# tx.net
KiCad netlist of a schematic drawn in EAGLE
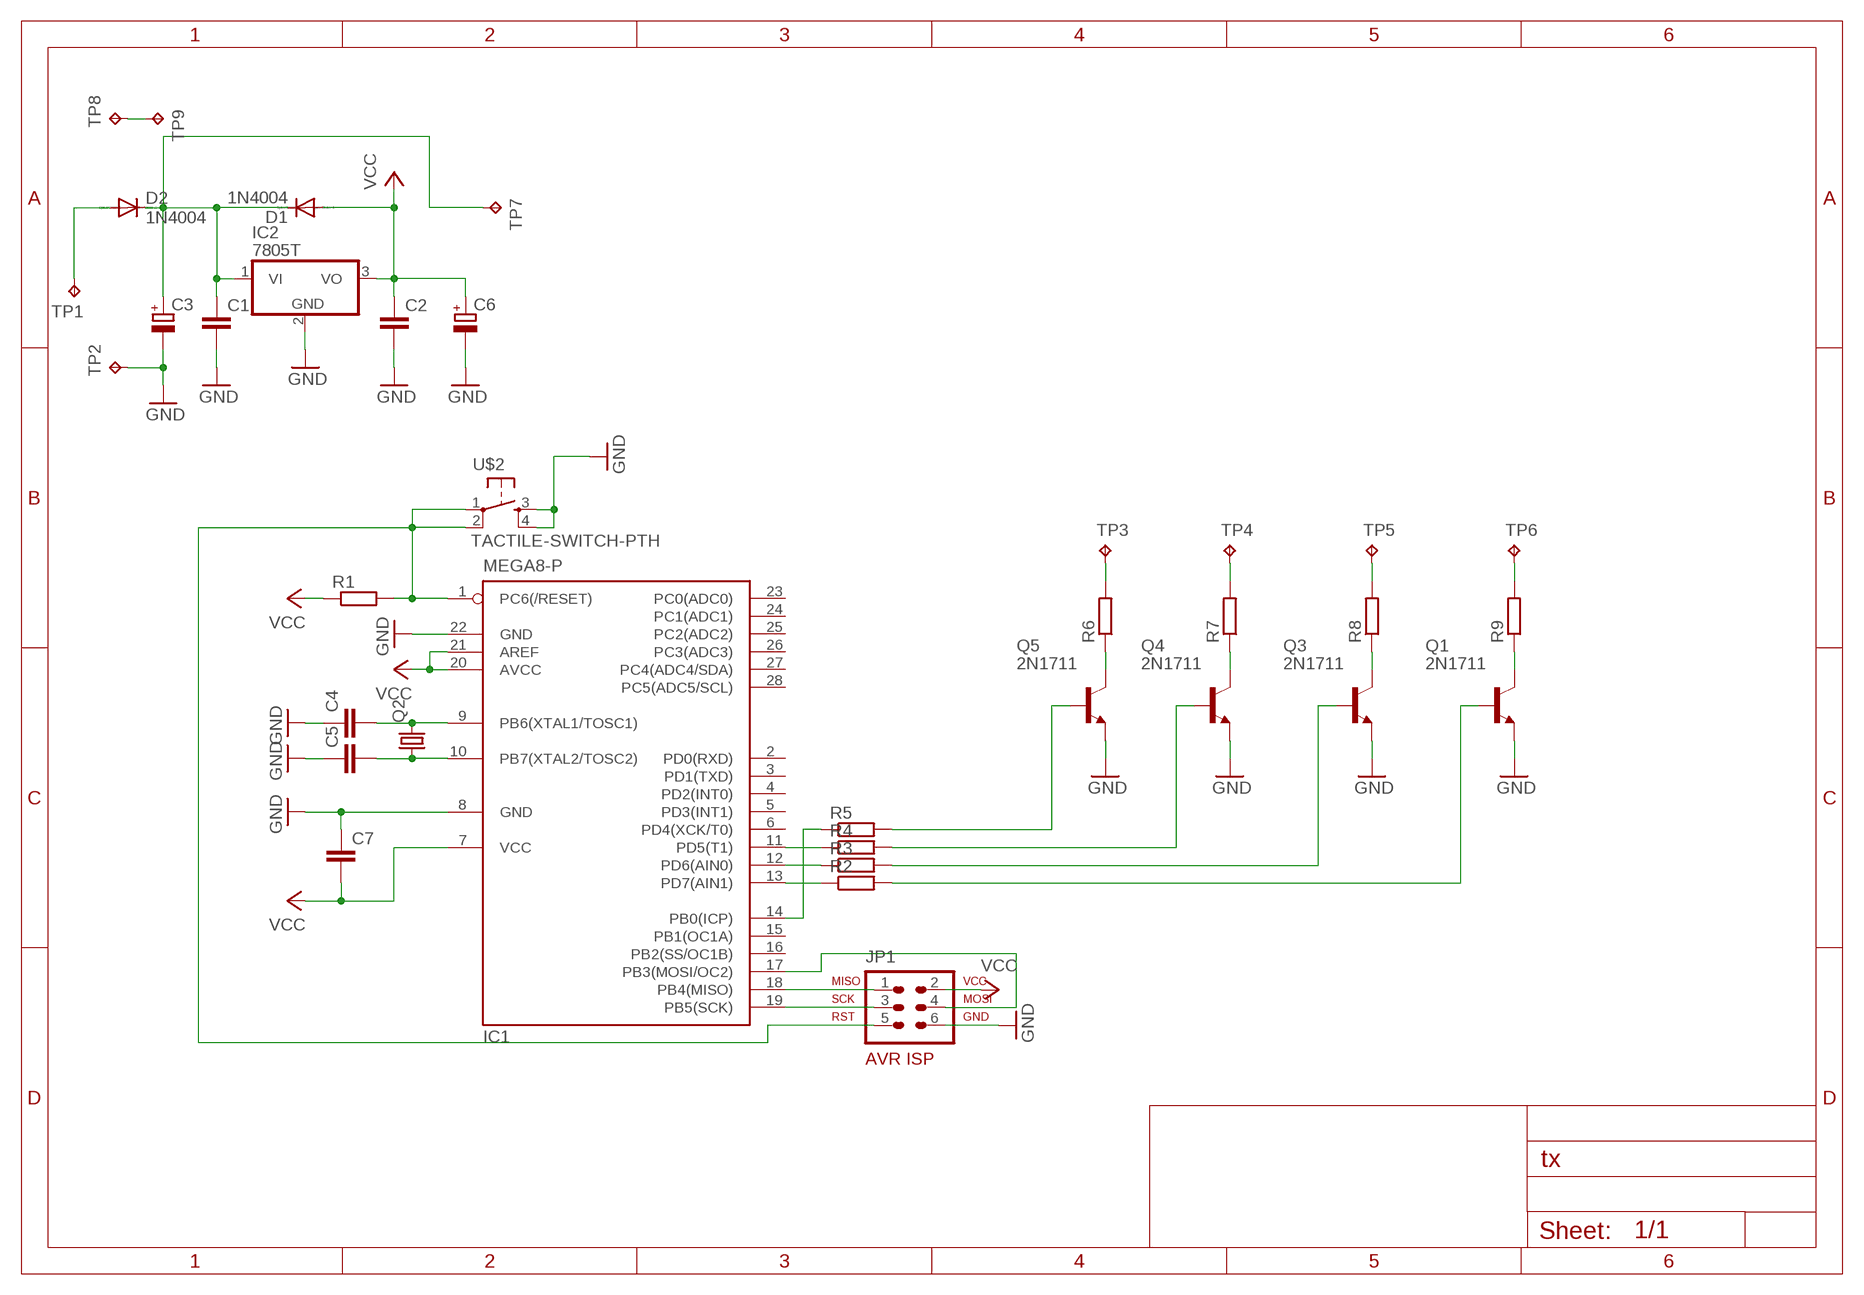
[diagram p0: schematic, sheet 1]

(export (version "E")
  (design (tool "Eeschema 10.0.6"))
  (components
    (comp (ref "C1")
      (value "C-EU050-030X075")
      (footprint "eagle-import:C050-030X075")
      (libsource (lib "eagle-import") (part "C-EU050-030X075"))
    )
    (comp (ref "C2")
      (value "C-EU050-030X075")
      (footprint "eagle-import:C050-030X075")
      (libsource (lib "eagle-import") (part "C-EU050-030X075"))
    )
    (comp (ref "C3")
      (value "CPOL-EUE3.5-8")
      (footprint "eagle-import:E3,5-8")
      (libsource (lib "eagle-import") (part "CPOL-EUE3.5-8"))
    )
    (comp (ref "C4")
      (value "C-EU050-030X075")
      (footprint "eagle-import:C050-030X075")
      (libsource (lib "eagle-import") (part "C-EU050-030X075"))
    )
    (comp (ref "C5")
      (value "C-EU050-030X075")
      (footprint "eagle-import:C050-030X075")
      (libsource (lib "eagle-import") (part "C-EU050-030X075"))
    )
    (comp (ref "C6")
      (value "CPOL-EUE3.5-8")
      (footprint "eagle-import:E3,5-8")
      (libsource (lib "eagle-import") (part "CPOL-EUE3.5-8"))
    )
    (comp (ref "C7")
      (value "C-EU050-030X075")
      (footprint "eagle-import:C050-030X075")
      (libsource (lib "eagle-import") (part "C-EU050-030X075"))
    )
    (comp (ref "D1")
      (value "1N4004")
      (footprint "eagle-import:DO41-10")
      (libsource (lib "eagle-import") (part "1N4004"))
    )
    (comp (ref "D2")
      (value "1N4004")
      (footprint "eagle-import:DO41-10")
      (libsource (lib "eagle-import") (part "1N4004"))
    )
    (comp (ref "IC1")
      (value "MEGA8-P")
      (footprint "eagle-import:DIL28-3")
      (libsource (lib "eagle-import") (part "MEGA8-P"))
    )
    (comp (ref "IC2")
      (value "7805T")
      (footprint "eagle-import:TO220H")
      (libsource (lib "eagle-import") (part "78T05"))
    )
    (comp (ref "JP1")
      (value "AVR-ISP-6HORZ")
      (footprint "eagle-import:AVR-ISP-6R")
      (libsource (lib "eagle-import") (part "AVR-ISP-6HORZ"))
    )
    (comp (ref "Q1")
      (value "2N1711")
      (footprint "eagle-import:TO39")
      (libsource (lib "eagle-import") (part "2N1711"))
    )
    (comp (ref "Q2")
      (value "CRYSTALHC49U70")
      (footprint "eagle-import:HC49U70")
      (libsource (lib "eagle-import") (part "CRYSTALHC49U70"))
    )
    (comp (ref "Q3")
      (value "2N1711")
      (footprint "eagle-import:TO39")
      (libsource (lib "eagle-import") (part "2N1711"))
    )
    (comp (ref "Q4")
      (value "2N1711")
      (footprint "eagle-import:TO39")
      (libsource (lib "eagle-import") (part "2N1711"))
    )
    (comp (ref "Q5")
      (value "2N1711")
      (footprint "eagle-import:TO39")
      (libsource (lib "eagle-import") (part "2N1711"))
    )
    (comp (ref "R1")
      (value "R-EU_0204/7")
      (footprint "eagle-import:0204_7")
      (libsource (lib "eagle-import") (part "R-EU_0204/7"))
    )
    (comp (ref "R2")
      (value "R-EU_0204/7")
      (footprint "eagle-import:0204_7")
      (libsource (lib "eagle-import") (part "R-EU_0204/7"))
    )
    (comp (ref "R3")
      (value "R-EU_0204/7")
      (footprint "eagle-import:0204_7")
      (libsource (lib "eagle-import") (part "R-EU_0204/7"))
    )
    (comp (ref "R4")
      (value "R-EU_0204/7")
      (footprint "eagle-import:0204_7")
      (libsource (lib "eagle-import") (part "R-EU_0204/7"))
    )
    (comp (ref "R5")
      (value "R-EU_0204/7")
      (footprint "eagle-import:0204_7")
      (libsource (lib "eagle-import") (part "R-EU_0204/7"))
    )
    (comp (ref "R6")
      (value "R-EU_0204/7")
      (footprint "eagle-import:0204_7")
      (libsource (lib "eagle-import") (part "R-EU_0204/7"))
    )
    (comp (ref "R7")
      (value "R-EU_0204/7")
      (footprint "eagle-import:0204_7")
      (libsource (lib "eagle-import") (part "R-EU_0204/7"))
    )
    (comp (ref "R8")
      (value "R-EU_0204/7")
      (footprint "eagle-import:0204_7")
      (libsource (lib "eagle-import") (part "R-EU_0204/7"))
    )
    (comp (ref "R9")
      (value "R-EU_0204/7")
      (footprint "eagle-import:0204_7")
      (libsource (lib "eagle-import") (part "R-EU_0204/7"))
    )
    (comp (ref "TP1")
      (value "TPPAD1-13Y")
      (footprint "eagle-import:P1-13Y")
      (libsource (lib "eagle-import") (part "TPPAD1-13Y"))
    )
    (comp (ref "TP2")
      (value "TPPAD1-13Y")
      (footprint "eagle-import:P1-13Y")
      (libsource (lib "eagle-import") (part "TPPAD1-13Y"))
    )
    (comp (ref "TP3")
      (value "TPPAD1-13Y")
      (footprint "eagle-import:P1-13Y")
      (libsource (lib "eagle-import") (part "TPPAD1-13Y"))
    )
    (comp (ref "TP4")
      (value "TPPAD1-13Y")
      (footprint "eagle-import:P1-13Y")
      (libsource (lib "eagle-import") (part "TPPAD1-13Y"))
    )
    (comp (ref "TP5")
      (value "TPPAD1-13Y")
      (footprint "eagle-import:P1-13Y")
      (libsource (lib "eagle-import") (part "TPPAD1-13Y"))
    )
    (comp (ref "TP6")
      (value "TPPAD1-13Y")
      (footprint "eagle-import:P1-13Y")
      (libsource (lib "eagle-import") (part "TPPAD1-13Y"))
    )
    (comp (ref "TP7")
      (value "TPPAD1-13Y")
      (footprint "eagle-import:P1-13Y")
      (libsource (lib "eagle-import") (part "TPPAD1-13Y"))
    )
    (comp (ref "TP8")
      (value "TPPAD1-13Y")
      (footprint "eagle-import:P1-13Y")
      (libsource (lib "eagle-import") (part "TPPAD1-13Y"))
    )
    (comp (ref "TP9")
      (value "TPPAD1-13Y")
      (footprint "eagle-import:P1-13Y")
      (libsource (lib "eagle-import") (part "TPPAD1-13Y"))
    )
    (comp (ref "U$2")
      (value "TACTILE-SWITCH-PTH")
      (footprint "eagle-import:TAC-SWITCH-PTH")
      (libsource (lib "eagle-import") (part "TACTILE-SWITCH-PTH"))
    )
  )
  (nets
    (net (code "1") (name "GND") (class "Default")
      (node (ref "C1") (pin "2") (pinfunction "2_2") (pintype "passive"))
      (node (ref "C2") (pin "2") (pinfunction "2_2") (pintype "passive"))
      (node (ref "C3") (pin "-") (pinfunction "-_-") (pintype "passive"))
      (node (ref "C4") (pin "1") (pinfunction "1_1") (pintype "passive"))
      (node (ref "C5") (pin "1") (pinfunction "1_1") (pintype "passive"))
      (node (ref "C6") (pin "-") (pinfunction "-_-") (pintype "passive"))
      (node (ref "C7") (pin "1") (pinfunction "1_1") (pintype "passive"))
      (node (ref "IC1") (pin "22") (pinfunction "GND_22") (pintype "power_in"))
      (node (ref "IC1") (pin "8") (pinfunction "GND_8") (pintype "power_in"))
      (node (ref "IC2") (pin "2") (pinfunction "GND_2") (pintype "passive"))
      (node (ref "JP1") (pin "6") (pinfunction "6_6") (pintype "passive"))
      (node (ref "Q1") (pin "1") (pinfunction "E_1") (pintype "passive"))
      (node (ref "Q3") (pin "1") (pinfunction "E_1") (pintype "passive"))
      (node (ref "Q4") (pin "1") (pinfunction "E_1") (pintype "passive"))
      (node (ref "Q5") (pin "1") (pinfunction "E_1") (pintype "passive"))
      (node (ref "TP2") (pin "TP") (pinfunction "TP_TP") (pintype "input"))
      (node (ref "U$2") (pin "3") (pinfunction "3_3") (pintype "passive"))
      (node (ref "U$2") (pin "4") (pinfunction "4_4") (pintype "passive"))
    )
    (net (code "2") (name "Net-(D2-PadA)") (class "Default")
      (node (ref "D2") (pin "A") (pinfunction "A_A") (pintype "passive"))
      (node (ref "TP1") (pin "TP") (pinfunction "TP_TP") (pintype "input"))
    )
    (net (code "3") (name "Net-(IC1-PB0(ICP))") (class "Default")
      (node (ref "IC1") (pin "14") (pinfunction "PB0(ICP)_14") (pintype "bidirectional"))
      (node (ref "R5") (pin "1") (pinfunction "1_1") (pintype "passive"))
    )
    (net (code "4") (name "Net-(IC1-PB3(MOSI{slash}OC2))") (class "Default")
      (node (ref "IC1") (pin "17") (pinfunction "PB3(MOSI/OC2)_17") (pintype "bidirectional"))
      (node (ref "JP1") (pin "4") (pinfunction "4_4") (pintype "passive"))
    )
    (net (code "5") (name "Net-(IC1-PB4(MISO))") (class "Default")
      (node (ref "IC1") (pin "18") (pinfunction "PB4(MISO)_18") (pintype "bidirectional"))
      (node (ref "JP1") (pin "1") (pinfunction "1_1") (pintype "passive"))
    )
    (net (code "6") (name "Net-(IC1-PB5(SCK))") (class "Default")
      (node (ref "IC1") (pin "19") (pinfunction "PB5(SCK)_19") (pintype "bidirectional"))
      (node (ref "JP1") (pin "3") (pinfunction "3_3") (pintype "passive"))
    )
    (net (code "7") (name "Net-(IC1-PB6(XTAL1{slash}TOSC1))") (class "Default")
      (node (ref "C4") (pin "2") (pinfunction "2_2") (pintype "passive"))
      (node (ref "IC1") (pin "9") (pinfunction "PB6(XTAL1/TOSC1)_9") (pintype "bidirectional"))
      (node (ref "Q2") (pin "2") (pinfunction "2_2") (pintype "passive"))
    )
    (net (code "8") (name "Net-(IC1-PB7(XTAL2{slash}TOSC2))") (class "Default")
      (node (ref "C5") (pin "2") (pinfunction "2_2") (pintype "passive"))
      (node (ref "IC1") (pin "10") (pinfunction "PB7(XTAL2/TOSC2)_10") (pintype "bidirectional"))
      (node (ref "Q2") (pin "1") (pinfunction "1_1") (pintype "passive"))
    )
    (net (code "9") (name "Net-(IC1-PC6({slash}RESET))") (class "Default")
      (node (ref "IC1") (pin "1") (pinfunction "PC6(/RESET)_1") (pintype "bidirectional"))
      (node (ref "JP1") (pin "5") (pinfunction "5_5") (pintype "passive"))
      (node (ref "R1") (pin "2") (pinfunction "2_2") (pintype "passive"))
      (node (ref "U$2") (pin "1") (pinfunction "1_1") (pintype "passive"))
      (node (ref "U$2") (pin "2") (pinfunction "2_2") (pintype "passive"))
    )
    (net (code "10") (name "Net-(IC1-PD5(T1))") (class "Default")
      (node (ref "IC1") (pin "11") (pinfunction "PD5(T1)_11") (pintype "bidirectional"))
      (node (ref "R4") (pin "1") (pinfunction "1_1") (pintype "passive"))
    )
    (net (code "11") (name "Net-(IC1-PD6(AIN0))") (class "Default")
      (node (ref "IC1") (pin "12") (pinfunction "PD6(AIN0)_12") (pintype "bidirectional"))
      (node (ref "R3") (pin "1") (pinfunction "1_1") (pintype "passive"))
    )
    (net (code "12") (name "Net-(IC1-PD7(AIN1))") (class "Default")
      (node (ref "IC1") (pin "13") (pinfunction "PD7(AIN1)_13") (pintype "bidirectional"))
      (node (ref "R2") (pin "1") (pinfunction "1_1") (pintype "passive"))
    )
    (net (code "13") (name "Net-(IC2-VI)") (class "Default")
      (node (ref "C1") (pin "1") (pinfunction "1_1") (pintype "passive"))
      (node (ref "C3") (pin "+") (pinfunction "+_+") (pintype "passive"))
      (node (ref "D1") (pin "C") (pinfunction "C_C") (pintype "passive"))
      (node (ref "D2") (pin "C") (pinfunction "C_C") (pintype "passive"))
      (node (ref "IC2") (pin "1") (pinfunction "VI_1") (pintype "input"))
      (node (ref "TP7") (pin "TP") (pinfunction "TP_TP") (pintype "input"))
    )
    (net (code "14") (name "Net-(Q1-B)") (class "Default")
      (node (ref "Q1") (pin "2") (pinfunction "B_2") (pintype "passive"))
      (node (ref "R2") (pin "2") (pinfunction "2_2") (pintype "passive"))
    )
    (net (code "15") (name "Net-(Q1-C)") (class "Default")
      (node (ref "Q1") (pin "3") (pinfunction "C_3") (pintype "passive"))
      (node (ref "R9") (pin "1") (pinfunction "1_1") (pintype "passive"))
    )
    (net (code "16") (name "Net-(Q3-B)") (class "Default")
      (node (ref "Q3") (pin "2") (pinfunction "B_2") (pintype "passive"))
      (node (ref "R3") (pin "2") (pinfunction "2_2") (pintype "passive"))
    )
    (net (code "17") (name "Net-(Q3-C)") (class "Default")
      (node (ref "Q3") (pin "3") (pinfunction "C_3") (pintype "passive"))
      (node (ref "R8") (pin "1") (pinfunction "1_1") (pintype "passive"))
    )
    (net (code "18") (name "Net-(Q4-B)") (class "Default")
      (node (ref "Q4") (pin "2") (pinfunction "B_2") (pintype "passive"))
      (node (ref "R4") (pin "2") (pinfunction "2_2") (pintype "passive"))
    )
    (net (code "19") (name "Net-(Q4-C)") (class "Default")
      (node (ref "Q4") (pin "3") (pinfunction "C_3") (pintype "passive"))
      (node (ref "R7") (pin "1") (pinfunction "1_1") (pintype "passive"))
    )
    (net (code "20") (name "Net-(Q5-B)") (class "Default")
      (node (ref "Q5") (pin "2") (pinfunction "B_2") (pintype "passive"))
      (node (ref "R5") (pin "2") (pinfunction "2_2") (pintype "passive"))
    )
    (net (code "21") (name "Net-(Q5-C)") (class "Default")
      (node (ref "Q5") (pin "3") (pinfunction "C_3") (pintype "passive"))
      (node (ref "R6") (pin "1") (pinfunction "1_1") (pintype "passive"))
    )
    (net (code "22") (name "Net-(R6-Pad2)") (class "Default")
      (node (ref "R6") (pin "2") (pinfunction "2_2") (pintype "passive"))
      (node (ref "TP3") (pin "TP") (pinfunction "TP_TP") (pintype "input"))
    )
    (net (code "23") (name "Net-(R7-Pad2)") (class "Default")
      (node (ref "R7") (pin "2") (pinfunction "2_2") (pintype "passive"))
      (node (ref "TP4") (pin "TP") (pinfunction "TP_TP") (pintype "input"))
    )
    (net (code "24") (name "Net-(R8-Pad2)") (class "Default")
      (node (ref "R8") (pin "2") (pinfunction "2_2") (pintype "passive"))
      (node (ref "TP5") (pin "TP") (pinfunction "TP_TP") (pintype "input"))
    )
    (net (code "25") (name "Net-(R9-Pad2)") (class "Default")
      (node (ref "R9") (pin "2") (pinfunction "2_2") (pintype "passive"))
      (node (ref "TP6") (pin "TP") (pinfunction "TP_TP") (pintype "input"))
    )
    (net (code "26") (name "Net-(TP8-PadTP)") (class "Default")
      (node (ref "TP8") (pin "TP") (pinfunction "TP_TP") (pintype "input"))
      (node (ref "TP9") (pin "TP") (pinfunction "TP_TP") (pintype "input"))
    )
    (net (code "27") (name "VCC") (class "Default")
      (node (ref "C2") (pin "1") (pinfunction "1_1") (pintype "passive"))
      (node (ref "C6") (pin "+") (pinfunction "+_+") (pintype "passive"))
      (node (ref "C7") (pin "2") (pinfunction "2_2") (pintype "passive"))
      (node (ref "D1") (pin "A") (pinfunction "A_A") (pintype "passive"))
      (node (ref "IC1") (pin "20") (pinfunction "AVCC_20") (pintype "power_in"))
      (node (ref "IC1") (pin "21") (pinfunction "AREF_21") (pintype "passive"))
      (node (ref "IC1") (pin "7") (pinfunction "VCC_7") (pintype "power_in"))
      (node (ref "IC2") (pin "3") (pinfunction "VO_3") (pintype "passive"))
      (node (ref "JP1") (pin "2") (pinfunction "2_2") (pintype "passive"))
      (node (ref "R1") (pin "1") (pinfunction "1_1") (pintype "passive"))
    )
    (net (code "28") (name "unconnected-(IC1-PB1(OC1A)-Pad15)") (class "Default")
      (node (ref "IC1") (pin "15") (pinfunction "PB1(OC1A)_15") (pintype "bidirectional"))
    )
    (net (code "29") (name "unconnected-(IC1-PB2(SS{slash}OC1B)-Pad16)") (class "Default")
      (node (ref "IC1") (pin "16") (pinfunction "PB2(SS/OC1B)_16") (pintype "bidirectional"))
    )
    (net (code "30") (name "unconnected-(IC1-PC0(ADC0)-Pad23)") (class "Default")
      (node (ref "IC1") (pin "23") (pinfunction "PC0(ADC0)_23") (pintype "bidirectional"))
    )
    (net (code "31") (name "unconnected-(IC1-PC1(ADC1)-Pad24)") (class "Default")
      (node (ref "IC1") (pin "24") (pinfunction "PC1(ADC1)_24") (pintype "bidirectional"))
    )
    (net (code "32") (name "unconnected-(IC1-PC2(ADC2)-Pad25)") (class "Default")
      (node (ref "IC1") (pin "25") (pinfunction "PC2(ADC2)_25") (pintype "bidirectional"))
    )
    (net (code "33") (name "unconnected-(IC1-PC3(ADC3)-Pad26)") (class "Default")
      (node (ref "IC1") (pin "26") (pinfunction "PC3(ADC3)_26") (pintype "bidirectional"))
    )
    (net (code "34") (name "unconnected-(IC1-PC4(ADC4{slash}SDA)-Pad27)") (class "Default")
      (node (ref "IC1") (pin "27") (pinfunction "PC4(ADC4/SDA)_27") (pintype "bidirectional"))
    )
    (net (code "35") (name "unconnected-(IC1-PC5(ADC5{slash}SCL)-Pad28)") (class "Default")
      (node (ref "IC1") (pin "28") (pinfunction "PC5(ADC5/SCL)_28") (pintype "bidirectional"))
    )
    (net (code "36") (name "unconnected-(IC1-PD0(RXD)-Pad2)") (class "Default")
      (node (ref "IC1") (pin "2") (pinfunction "PD0(RXD)_2") (pintype "bidirectional"))
    )
    (net (code "37") (name "unconnected-(IC1-PD1(TXD)-Pad3)") (class "Default")
      (node (ref "IC1") (pin "3") (pinfunction "PD1(TXD)_3") (pintype "bidirectional"))
    )
    (net (code "38") (name "unconnected-(IC1-PD2(INT0)-Pad4)") (class "Default")
      (node (ref "IC1") (pin "4") (pinfunction "PD2(INT0)_4") (pintype "bidirectional"))
    )
    (net (code "39") (name "unconnected-(IC1-PD3(INT1)-Pad5)") (class "Default")
      (node (ref "IC1") (pin "5") (pinfunction "PD3(INT1)_5") (pintype "bidirectional"))
    )
    (net (code "40") (name "unconnected-(IC1-PD4(XCK{slash}T0)-Pad6)") (class "Default")
      (node (ref "IC1") (pin "6") (pinfunction "PD4(XCK/T0)_6") (pintype "bidirectional"))
    )
  )
)
